# pmm.net
KiCad netlist of a schematic drawn in EAGLE
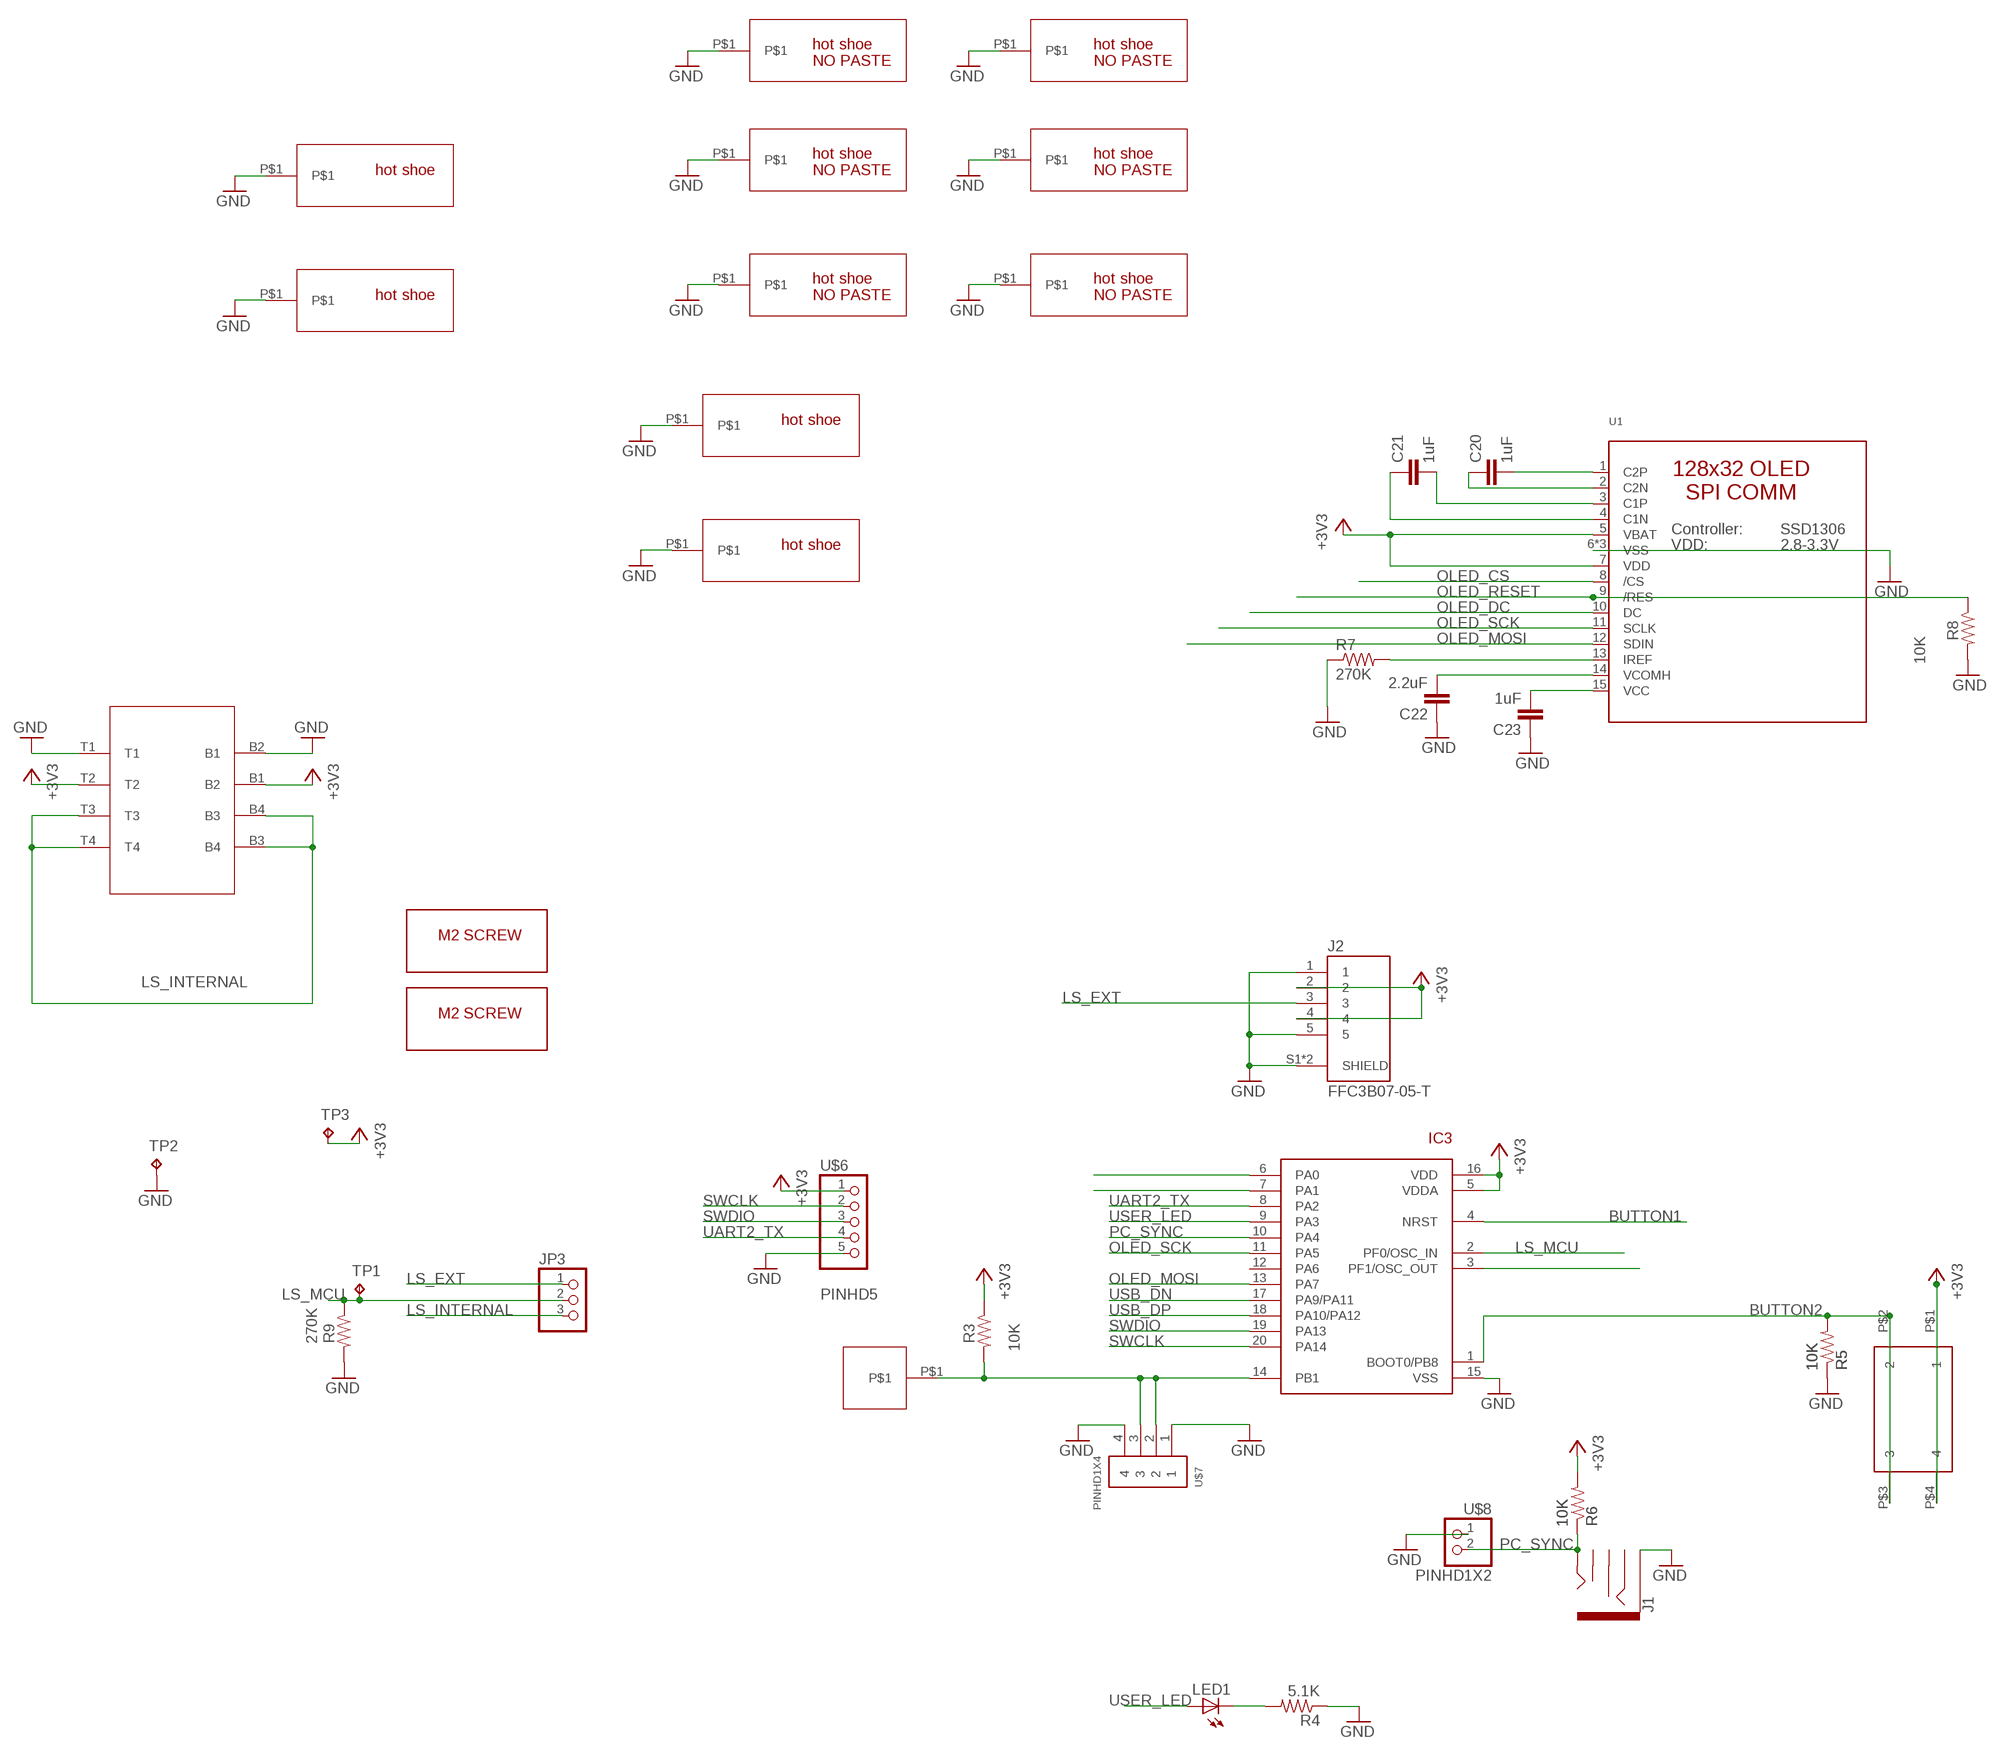
[diagram p0: schematic, sheet 1, part 1 of 2]
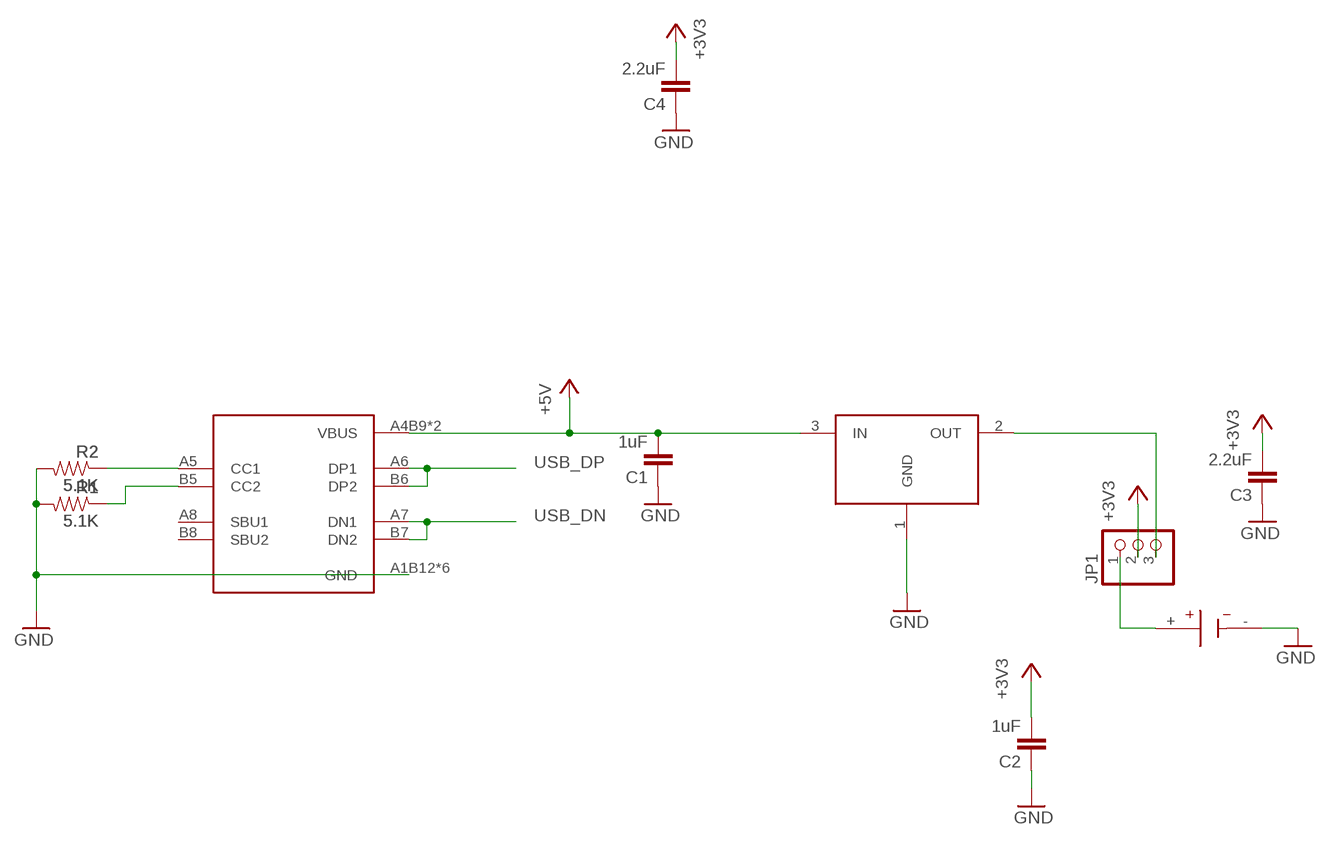
[diagram p1: schematic, sheet 1, part 2 of 2]

(export (version "E")
  (design (tool "Eeschema 10.0.6"))
  (components
    (comp (ref "BT1")
      (value "BU2032SM-G")
      (footprint "eagle-import:BAT_BU2032SM-G")
      (fields (field (name "MF") "MPD"))
      (libsource (lib "eagle-import") (part "BU2032SM-G"))
    )
    (comp (ref "C1")
      (value "1uF")
      (footprint "eagle-import:0805")
      (libsource (lib "eagle-import") (part "CAP0805"))
    )
    (comp (ref "C2")
      (value "1uF")
      (footprint "eagle-import:0805")
      (libsource (lib "eagle-import") (part "CAP0805"))
    )
    (comp (ref "C3")
      (value "2.2uF")
      (footprint "eagle-import:0805")
      (libsource (lib "eagle-import") (part "CAP0805"))
    )
    (comp (ref "C4")
      (value "2.2uF")
      (footprint "eagle-import:0805")
      (libsource (lib "eagle-import") (part "CAP0805"))
    )
    (comp (ref "C20")
      (value "1uF")
      (footprint "eagle-import:0805")
      (libsource (lib "eagle-import") (part "CAP0805"))
    )
    (comp (ref "C21")
      (value "1uF")
      (footprint "eagle-import:0805")
      (libsource (lib "eagle-import") (part "CAP0805"))
    )
    (comp (ref "C22")
      (value "2.2uF")
      (footprint "eagle-import:0805")
      (libsource (lib "eagle-import") (part "CAP0805"))
    )
    (comp (ref "C23")
      (value "1uF")
      (footprint "eagle-import:0805")
      (libsource (lib "eagle-import") (part "CAP0805"))
    )
    (comp (ref "IC3")
      (value "STM32F042F4")
      (footprint "eagle-import:TSSOP20")
      (libsource (lib "eagle-import") (part "STM32F042F4"))
    )
    (comp (ref "J1")
      (value "AUDIO_JACK_3.5MM_PTH")
      (footprint "eagle-import:AUDIO-JACK")
      (libsource (lib "eagle-import") (part "AUDIO_JACK_3.5MM_PTH"))
    )
    (comp (ref "J2")
      (value "FFC3B07-05-T")
      (footprint "eagle-import:GCT_FFC3B07-05-T")
      (fields (field (name "MF") "Global Connector Technology"))
      (libsource (lib "eagle-import") (part "FFC3B07-05-T"))
    )
    (comp (ref "JP1")
      (value "PINHD-1X3CB")
      (footprint "eagle-import:1X03-CLEANBIG")
      (libsource (lib "eagle-import") (part "PINHD-1X3CB"))
    )
    (comp (ref "JP3")
      (value "PINHD-1X3CB")
      (footprint "eagle-import:1X03-CLEANBIG")
      (libsource (lib "eagle-import") (part "PINHD-1X3CB"))
    )
    (comp (ref "LED1")
      (value "LEDCHIP-LED0805")
      (footprint "eagle-import:CHIP-LED0805")
      (libsource (lib "eagle-import") (part "LEDCHIP-LED0805"))
    )
    (comp (ref "R1")
      (value "5.1K")
      (footprint "eagle-import:0805")
      (libsource (lib "eagle-import") (part "joyAnalog_RESISTOR0805-RES"))
    )
    (comp (ref "R2")
      (value "5.1K")
      (footprint "eagle-import:0805")
      (libsource (lib "eagle-import") (part "joyAnalog_RESISTOR0805-RES"))
    )
    (comp (ref "R3")
      (value "10K")
      (footprint "eagle-import:0805")
      (libsource (lib "eagle-import") (part "joyAnalog_RESISTOR0805-RES"))
    )
    (comp (ref "R4")
      (value "5.1K")
      (footprint "eagle-import:0805")
      (libsource (lib "eagle-import") (part "RESISTOR0805-RES"))
    )
    (comp (ref "R5")
      (value "10K")
      (footprint "eagle-import:0805")
      (libsource (lib "eagle-import") (part "joyAnalog_RESISTOR0805-RES"))
    )
    (comp (ref "R6")
      (value "10K")
      (footprint "eagle-import:0805")
      (libsource (lib "eagle-import") (part "joyAnalog_RESISTOR0805-RES"))
    )
    (comp (ref "R7")
      (value "270K")
      (footprint "eagle-import:0805")
      (libsource (lib "eagle-import") (part "RESISTOR0805-RES"))
    )
    (comp (ref "R8")
      (value "10K")
      (footprint "eagle-import:0805")
      (libsource (lib "eagle-import") (part "joyAnalog_RESISTOR0805-RES"))
    )
    (comp (ref "R9")
      (value "270K")
      (footprint "eagle-import:0805")
      (libsource (lib "eagle-import") (part "joyAnalog_RESISTOR0805-RES"))
    )
    (comp (ref "SW4")
      (value "324_SW")
      (footprint "eagle-import:342_SWICH_FOOT")
      (libsource (lib "eagle-import") (part "324_SW"))
    )
    (comp (ref "TP1")
      (value "TPTP18R")
      (footprint "eagle-import:TP18R")
      (libsource (lib "eagle-import") (part "TPTP18R"))
    )
    (comp (ref "TP2")
      (value "TPTP18R")
      (footprint "eagle-import:TP18R")
      (libsource (lib "eagle-import") (part "TPTP18R"))
    )
    (comp (ref "TP3")
      (value "TPTP18R")
      (footprint "eagle-import:TP18R")
      (libsource (lib "eagle-import") (part "TPTP18R"))
    )
    (comp (ref "U$1")
      (value "M2_SCREW_DEV")
      (footprint "eagle-import:M2_SCREW_FOOT")
      (libsource (lib "eagle-import") (part "M2_SCREW_DEV"))
    )
    (comp (ref "U$2")
      (value "SPRING_CONTACT")
      (footprint "eagle-import:SPRING_CONTACT")
      (libsource (lib "eagle-import") (part "SPRING_CONTACT"))
    )
    (comp (ref "U$3")
      (value "HOTSHOE")
      (footprint "eagle-import:HOTSHOE_RAIL")
      (libsource (lib "eagle-import") (part "HOTSHOE"))
    )
    (comp (ref "U$4")
      (value "HOTSHOE")
      (footprint "eagle-import:HOTSHOE_RAIL")
      (libsource (lib "eagle-import") (part "HOTSHOE"))
    )
    (comp (ref "U$5")
      (value "HOTSHOE_NOPASTE")
      (footprint "eagle-import:HOTSHOE_RAIL_NOPASTE")
      (libsource (lib "eagle-import") (part "HOTSHOE_NOPASTE"))
    )
    (comp (ref "U$6")
      (value "PINHD5")
      (footprint "eagle-import:1X05")
      (libsource (lib "eagle-import") (part "PINHD5"))
    )
    (comp (ref "U$7")
      (value "PINHD1X4")
      (footprint "eagle-import:1X04-CLEANBIG")
      (libsource (lib "eagle-import") (part "PINHD1X4"))
    )
    (comp (ref "U$8")
      (value "PINHD1X2")
      (footprint "eagle-import:1X02")
      (libsource (lib "eagle-import") (part "PINHD1X2"))
    )
    (comp (ref "U$9")
      (value "HOTSHOE_NOPASTE")
      (footprint "eagle-import:HOTSHOE_RAIL_NOPASTE")
      (libsource (lib "eagle-import") (part "HOTSHOE_NOPASTE"))
    )
    (comp (ref "U$10")
      (value "HOTSHOE_NOPASTE")
      (footprint "eagle-import:HOTSHOE_RAIL_NOPASTE")
      (libsource (lib "eagle-import") (part "HOTSHOE_NOPASTE"))
    )
    (comp (ref "U$11")
      (value "HOTSHOE_NOPASTE")
      (footprint "eagle-import:HOTSHOE_RAIL_NOPASTE")
      (libsource (lib "eagle-import") (part "HOTSHOE_NOPASTE"))
    )
    (comp (ref "U$12")
      (value "M2_SCREW_DEV")
      (footprint "eagle-import:M2_SCREW_FOOT")
      (libsource (lib "eagle-import") (part "M2_SCREW_DEV"))
    )
    (comp (ref "U$13")
      (value "HOTSHOE_NOPASTE")
      (footprint "eagle-import:HOTSHOE_RAIL_NOPASTE")
      (libsource (lib "eagle-import") (part "HOTSHOE_NOPASTE"))
    )
    (comp (ref "U$14")
      (value "HOTSHOE")
      (footprint "eagle-import:HOTSHOE_RAIL")
      (libsource (lib "eagle-import") (part "HOTSHOE"))
    )
    (comp (ref "U$15")
      (value "HOTSHOE_NOPASTE")
      (footprint "eagle-import:HOTSHOE_RAIL_NOPASTE")
      (libsource (lib "eagle-import") (part "HOTSHOE_NOPASTE"))
    )
    (comp (ref "U$16")
      (value "HOTSHOE")
      (footprint "eagle-import:HOTSHOE_RAIL")
      (libsource (lib "eagle-import") (part "HOTSHOE"))
    )
    (comp (ref "U$17")
      (value "LS_HOLE")
      (footprint "eagle-import:LS")
      (libsource (lib "eagle-import") (part "LS_HOLE"))
    )
    (comp (ref "U1")
      (value "LUL_DISP_OLED_UG-2864HSWEG01")
      (footprint "eagle-import:LUL_UG-2864HSWEG01_1.3_WRAPAROUND")
      (libsource (lib "eagle-import") (part "LUL_DISP_OLED_UG-2864HSWEG01"))
    )
    (comp (ref "U2")
      (value "USBC_16P")
      (footprint "eagle-import:USBC_16P_FOOT")
      (libsource (lib "eagle-import") (part "USBC_16P"))
    )
    (comp (ref "U4")
      (value "XC6206_DEV")
      (footprint "eagle-import:SOT23R_INFINEON")
      (libsource (lib "eagle-import") (part "XC6206_DEV"))
    )
  )
  (nets
    (net (code "1") (name "+3V3") (class "Default")
      (node (ref "C2") (pin "2") (pinfunction "2_2") (pintype "passive"))
      (node (ref "C3") (pin "2") (pinfunction "2_2") (pintype "passive"))
      (node (ref "C4") (pin "2") (pinfunction "2_2") (pintype "passive"))
      (node (ref "IC3") (pin "16") (pinfunction "VDD_16") (pintype "bidirectional"))
      (node (ref "IC3") (pin "5") (pinfunction "VDDA_5") (pintype "bidirectional"))
      (node (ref "J2") (pin "2") (pinfunction "2_2") (pintype "passive"))
      (node (ref "J2") (pin "4") (pinfunction "4_4") (pintype "passive"))
      (node (ref "JP1") (pin "2") (pinfunction "2_2") (pintype "passive"))
      (node (ref "R3") (pin "1") (pinfunction "1_1") (pintype "passive"))
      (node (ref "R6") (pin "2") (pinfunction "2_2") (pintype "passive"))
      (node (ref "SW4") (pin "P$1") (pinfunction "1_P$1") (pintype "bidirectional"))
      (node (ref "SW4") (pin "P$4") (pinfunction "4_P$4") (pintype "bidirectional"))
      (node (ref "TP3") (pin "TP") (pinfunction "TP_TP") (pintype "input"))
      (node (ref "U$17") (pin "B1") (pinfunction "B2_B1") (pintype "bidirectional"))
      (node (ref "U$17") (pin "T2") (pinfunction "T2_T2") (pintype "bidirectional"))
      (node (ref "U$6") (pin "1") (pinfunction "1_1") (pintype "passive"))
      (node (ref "U1") (pin "5") (pinfunction "VBAT_5") (pintype "input"))
      (node (ref "U1") (pin "7") (pinfunction "VDD_7") (pintype "power_in"))
    )
    (net (code "2") (name "+5V") (class "Default")
      (node (ref "C1") (pin "2") (pinfunction "2_2") (pintype "passive"))
      (node (ref "U2") (pin "A4B9") (pinfunction "VBUS_A4B9") (pintype "bidirectional"))
      (node (ref "U2") (pin "B4A9") (pinfunction "VBUS_B4A9") (pintype "bidirectional"))
      (node (ref "U4") (pin "3") (pinfunction "IN_3") (pintype "bidirectional"))
    )
    (net (code "3") (name "/BUTTON1") (class "Default")
      (node (ref "IC3") (pin "4") (pinfunction "NRST_4") (pintype "bidirectional"))
    )
    (net (code "4") (name "/BUTTON2") (class "Default")
      (node (ref "IC3") (pin "1") (pinfunction "BOOT0/PB8_1") (pintype "bidirectional"))
      (node (ref "R5") (pin "2") (pinfunction "2_2") (pintype "passive"))
      (node (ref "SW4") (pin "P$2") (pinfunction "2_P$2") (pintype "bidirectional"))
      (node (ref "SW4") (pin "P$3") (pinfunction "3_P$3") (pintype "bidirectional"))
    )
    (net (code "5") (name "/LS_EXT") (class "Default")
      (node (ref "J2") (pin "3") (pinfunction "3_3") (pintype "passive"))
      (node (ref "JP3") (pin "1") (pinfunction "1_1") (pintype "passive"))
    )
    (net (code "6") (name "/LS_INTERNAL") (class "Default")
      (node (ref "JP3") (pin "3") (pinfunction "3_3") (pintype "passive"))
      (node (ref "U$17") (pin "B3") (pinfunction "B4_B3") (pintype "bidirectional"))
      (node (ref "U$17") (pin "B4") (pinfunction "B3_B4") (pintype "bidirectional"))
      (node (ref "U$17") (pin "T3") (pinfunction "T3_T3") (pintype "bidirectional"))
      (node (ref "U$17") (pin "T4") (pinfunction "T4_T4") (pintype "bidirectional"))
    )
    (net (code "7") (name "/LS_MCU") (class "Default")
      (node (ref "IC3") (pin "2") (pinfunction "PF0/OSC_IN_2") (pintype "bidirectional"))
      (node (ref "JP3") (pin "2") (pinfunction "2_2") (pintype "passive"))
      (node (ref "R9") (pin "1") (pinfunction "1_1") (pintype "passive"))
      (node (ref "TP1") (pin "TP") (pinfunction "TP_TP") (pintype "input"))
    )
    (net (code "8") (name "/OLED_CS") (class "Default")
      (node (ref "IC3") (pin "3") (pinfunction "PF1/OSC_OUT_3") (pintype "bidirectional"))
      (node (ref "U1") (pin "8") (pinfunction "/CS_8") (pintype "input"))
    )
    (net (code "9") (name "/OLED_DC") (class "Default")
      (node (ref "IC3") (pin "7") (pinfunction "PA1_7") (pintype "bidirectional"))
      (node (ref "U1") (pin "10") (pinfunction "DC_10") (pintype "input"))
    )
    (net (code "10") (name "/OLED_MOSI") (class "Default")
      (node (ref "IC3") (pin "13") (pinfunction "PA7_13") (pintype "bidirectional"))
      (node (ref "U1") (pin "12") (pinfunction "SDIN_12") (pintype "bidirectional"))
    )
    (net (code "11") (name "/OLED_RESET") (class "Default")
      (node (ref "IC3") (pin "6") (pinfunction "PA0_6") (pintype "bidirectional"))
      (node (ref "R8") (pin "1") (pinfunction "1_1") (pintype "passive"))
      (node (ref "U1") (pin "9") (pinfunction "/RES_9") (pintype "input"))
    )
    (net (code "12") (name "/OLED_SCK") (class "Default")
      (node (ref "IC3") (pin "11") (pinfunction "PA5_11") (pintype "bidirectional"))
      (node (ref "U1") (pin "11") (pinfunction "SCLK_11") (pintype "bidirectional"))
    )
    (net (code "13") (name "/PC_SYNC") (class "Default")
      (node (ref "IC3") (pin "10") (pinfunction "PA4_10") (pintype "bidirectional"))
      (node (ref "J1") (pin "TIP") (pinfunction "TIP_TIP") (pintype "bidirectional"))
      (node (ref "R6") (pin "1") (pinfunction "1_1") (pintype "passive"))
      (node (ref "U$8") (pin "2") (pinfunction "2_2") (pintype "passive"))
    )
    (net (code "14") (name "/SWCLK") (class "Default")
      (node (ref "IC3") (pin "20") (pinfunction "PA14_20") (pintype "bidirectional"))
      (node (ref "U$6") (pin "2") (pinfunction "2_2") (pintype "passive"))
    )
    (net (code "15") (name "/SWDIO") (class "Default")
      (node (ref "IC3") (pin "19") (pinfunction "PA13_19") (pintype "bidirectional"))
      (node (ref "U$6") (pin "3") (pinfunction "3_3") (pintype "passive"))
    )
    (net (code "16") (name "/UART2_TX") (class "Default")
      (node (ref "IC3") (pin "8") (pinfunction "PA2_8") (pintype "bidirectional"))
      (node (ref "U$6") (pin "4") (pinfunction "4_4") (pintype "passive"))
    )
    (net (code "17") (name "/USB_DN") (class "Default")
      (node (ref "IC3") (pin "17") (pinfunction "PA9/PA11_17") (pintype "bidirectional"))
      (node (ref "U2") (pin "A7") (pinfunction "DN1_A7") (pintype "bidirectional"))
      (node (ref "U2") (pin "B7") (pinfunction "DN2_B7") (pintype "bidirectional"))
    )
    (net (code "18") (name "/USB_DP") (class "Default")
      (node (ref "IC3") (pin "18") (pinfunction "PA10/PA12_18") (pintype "bidirectional"))
      (node (ref "U2") (pin "A6") (pinfunction "DP1_A6") (pintype "bidirectional"))
      (node (ref "U2") (pin "B6") (pinfunction "DP2_B6") (pintype "bidirectional"))
    )
    (net (code "19") (name "/USER_LED") (class "Default")
      (node (ref "IC3") (pin "9") (pinfunction "PA3_9") (pintype "bidirectional"))
      (node (ref "LED1") (pin "A") (pinfunction "A_A") (pintype "passive"))
    )
    (net (code "20") (name "GND") (class "Default")
      (node (ref "BT1") (pin "-") (pinfunction "-_-") (pintype "passive"))
      (node (ref "C1") (pin "1") (pinfunction "1_1") (pintype "passive"))
      (node (ref "C2") (pin "1") (pinfunction "1_1") (pintype "passive"))
      (node (ref "C22") (pin "1") (pinfunction "1_1") (pintype "passive"))
      (node (ref "C23") (pin "1") (pinfunction "1_1") (pintype "passive"))
      (node (ref "C3") (pin "1") (pinfunction "1_1") (pintype "passive"))
      (node (ref "C4") (pin "1") (pinfunction "1_1") (pintype "passive"))
      (node (ref "IC3") (pin "15") (pinfunction "VSS_15") (pintype "bidirectional"))
      (node (ref "J1") (pin "SLEEVE") (pinfunction "SLEEVE_SLEEVE") (pintype "bidirectional"))
      (node (ref "J2") (pin "1") (pinfunction "1_1") (pintype "passive"))
      (node (ref "J2") (pin "5") (pinfunction "5_5") (pintype "passive"))
      (node (ref "J2") (pin "S1") (pinfunction "SHIELD_S1") (pintype "passive"))
      (node (ref "J2") (pin "S2") (pinfunction "SHIELD_S2") (pintype "passive"))
      (node (ref "R1") (pin "2") (pinfunction "2_2") (pintype "passive"))
      (node (ref "R2") (pin "2") (pinfunction "2_2") (pintype "passive"))
      (node (ref "R4") (pin "1") (pinfunction "1_1") (pintype "passive"))
      (node (ref "R5") (pin "1") (pinfunction "1_1") (pintype "passive"))
      (node (ref "R7") (pin "1") (pinfunction "1_1") (pintype "passive"))
      (node (ref "R8") (pin "2") (pinfunction "2_2") (pintype "passive"))
      (node (ref "R9") (pin "2") (pinfunction "2_2") (pintype "passive"))
      (node (ref "TP2") (pin "TP") (pinfunction "TP_TP") (pintype "input"))
      (node (ref "U$10") (pin "P$1") (pinfunction "P$1_P$1") (pintype "bidirectional"))
      (node (ref "U$11") (pin "P$1") (pinfunction "P$1_P$1") (pintype "bidirectional"))
      (node (ref "U$13") (pin "P$1") (pinfunction "P$1_P$1") (pintype "bidirectional"))
      (node (ref "U$14") (pin "P$1") (pinfunction "P$1_P$1") (pintype "bidirectional"))
      (node (ref "U$15") (pin "P$1") (pinfunction "P$1_P$1") (pintype "bidirectional"))
      (node (ref "U$16") (pin "P$1") (pinfunction "P$1_P$1") (pintype "bidirectional"))
      (node (ref "U$17") (pin "B2") (pinfunction "B1_B2") (pintype "bidirectional"))
      (node (ref "U$17") (pin "T1") (pinfunction "T1_T1") (pintype "bidirectional"))
      (node (ref "U$3") (pin "P$1") (pinfunction "P$1_P$1") (pintype "bidirectional"))
      (node (ref "U$4") (pin "P$1") (pinfunction "P$1_P$1") (pintype "bidirectional"))
      (node (ref "U$5") (pin "P$1") (pinfunction "P$1_P$1") (pintype "bidirectional"))
      (node (ref "U$6") (pin "5") (pinfunction "5_5") (pintype "passive"))
      (node (ref "U$7") (pin "1") (pinfunction "1_1") (pintype "bidirectional"))
      (node (ref "U$7") (pin "4") (pinfunction "4_4") (pintype "bidirectional"))
      (node (ref "U$8") (pin "1") (pinfunction "1_1") (pintype "passive"))
      (node (ref "U$9") (pin "P$1") (pinfunction "P$1_P$1") (pintype "bidirectional"))
      (node (ref "U1") (pin "16") (pinfunction "VSS_16") (pintype "power_in"))
      (node (ref "U1") (pin "17") (pinfunction "VSS_17") (pintype "power_in"))
      (node (ref "U1") (pin "6") (pinfunction "VSS_6") (pintype "power_in"))
      (node (ref "U2") (pin "A1B12") (pinfunction "GND_A1B12") (pintype "bidirectional"))
      (node (ref "U2") (pin "B11A12") (pinfunction "GND_B11A12") (pintype "bidirectional"))
      (node (ref "U2") (pin "P$13") (pinfunction "GND_P$13") (pintype "bidirectional"))
      (node (ref "U2") (pin "P$14") (pinfunction "GND_P$14") (pintype "bidirectional"))
      (node (ref "U2") (pin "P$15") (pinfunction "GND_P$15") (pintype "bidirectional"))
      (node (ref "U2") (pin "P$16") (pinfunction "GND_P$16") (pintype "bidirectional"))
      (node (ref "U4") (pin "1") (pinfunction "GND_1") (pintype "bidirectional"))
    )
    (net (code "21") (name "Net-(BT1-Pad+)") (class "Default")
      (node (ref "BT1") (pin "+") (pinfunction "+_+") (pintype "passive"))
      (node (ref "JP1") (pin "1") (pinfunction "1_1") (pintype "passive"))
    )
    (net (code "22") (name "Net-(IC3-PB1)") (class "Default")
      (node (ref "IC3") (pin "14") (pinfunction "PB1_14") (pintype "bidirectional"))
      (node (ref "R3") (pin "2") (pinfunction "2_2") (pintype "passive"))
      (node (ref "U$2") (pin "P$1") (pinfunction "P$1_P$1") (pintype "bidirectional"))
      (node (ref "U$7") (pin "2") (pinfunction "2_2") (pintype "bidirectional"))
      (node (ref "U$7") (pin "3") (pinfunction "3_3") (pintype "bidirectional"))
    )
    (net (code "23") (name "Net-(LED1-PadC)") (class "Default")
      (node (ref "LED1") (pin "C") (pinfunction "C_C") (pintype "passive"))
      (node (ref "R4") (pin "2") (pinfunction "2_2") (pintype "passive"))
    )
    (net (code "24") (name "Net-(U1-C1N)") (class "Default")
      (node (ref "C21") (pin "1") (pinfunction "1_1") (pintype "passive"))
      (node (ref "U1") (pin "4") (pinfunction "C1N_4") (pintype "input"))
    )
    (net (code "25") (name "Net-(U1-C1P)") (class "Default")
      (node (ref "C21") (pin "2") (pinfunction "2_2") (pintype "passive"))
      (node (ref "U1") (pin "3") (pinfunction "C1P_3") (pintype "input"))
    )
    (net (code "26") (name "Net-(U1-C2N)") (class "Default")
      (node (ref "C20") (pin "1") (pinfunction "1_1") (pintype "passive"))
      (node (ref "U1") (pin "2") (pinfunction "C2N_2") (pintype "input"))
    )
    (net (code "27") (name "Net-(U1-C2P)") (class "Default")
      (node (ref "C20") (pin "2") (pinfunction "2_2") (pintype "passive"))
      (node (ref "U1") (pin "1") (pinfunction "C2P_1") (pintype "input"))
    )
    (net (code "28") (name "Net-(U1-IREF)") (class "Default")
      (node (ref "R7") (pin "2") (pinfunction "2_2") (pintype "passive"))
      (node (ref "U1") (pin "13") (pinfunction "IREF_13") (pintype "input"))
    )
    (net (code "29") (name "Net-(U1-VCC)") (class "Default")
      (node (ref "C23") (pin "2") (pinfunction "2_2") (pintype "passive"))
      (node (ref "U1") (pin "15") (pinfunction "VCC_15") (pintype "power_in"))
    )
    (net (code "30") (name "Net-(U1-VCOMH)") (class "Default")
      (node (ref "C22") (pin "2") (pinfunction "2_2") (pintype "passive"))
      (node (ref "U1") (pin "14") (pinfunction "VCOMH_14") (pintype "output"))
    )
    (net (code "31") (name "Net-(U2-CC1)") (class "Default")
      (node (ref "R2") (pin "1") (pinfunction "1_1") (pintype "passive"))
      (node (ref "U2") (pin "A5") (pinfunction "CC1_A5") (pintype "bidirectional"))
    )
    (net (code "32") (name "Net-(U2-CC2)") (class "Default")
      (node (ref "R1") (pin "1") (pinfunction "1_1") (pintype "passive"))
      (node (ref "U2") (pin "B5") (pinfunction "CC2_B5") (pintype "bidirectional"))
    )
    (net (code "33") (name "Net-(U4-OUT)") (class "Default")
      (node (ref "JP1") (pin "3") (pinfunction "3_3") (pintype "passive"))
      (node (ref "U4") (pin "2") (pinfunction "OUT_2") (pintype "bidirectional"))
    )
    (net (code "34") (name "unconnected-(IC3-PA6-Pad12)") (class "Default")
      (node (ref "IC3") (pin "12") (pinfunction "PA6_12") (pintype "bidirectional"))
    )
    (net (code "35") (name "unconnected-(J1-PadRING)") (class "Default")
      (node (ref "J1") (pin "RING") (pinfunction "RING_RING") (pintype "bidirectional"))
    )
    (net (code "36") (name "unconnected-(J1-PadRSH)") (class "Default")
      (node (ref "J1") (pin "RSH") (pinfunction "RSH_RSH") (pintype "bidirectional"))
    )
    (net (code "37") (name "unconnected-(J1-PadTSH)") (class "Default")
      (node (ref "J1") (pin "TSH") (pinfunction "TSH_TSH") (pintype "bidirectional"))
    )
    (net (code "38") (name "unconnected-(U2-SBU1-PadA8)") (class "Default")
      (node (ref "U2") (pin "A8") (pinfunction "SBU1_A8") (pintype "bidirectional"))
    )
    (net (code "39") (name "unconnected-(U2-SBU2-PadB8)") (class "Default")
      (node (ref "U2") (pin "B8") (pinfunction "SBU2_B8") (pintype "bidirectional"))
    )
  )
)
